# Pi1541_IEC.net
KiCad netlist of a schematic drawn in EAGLE
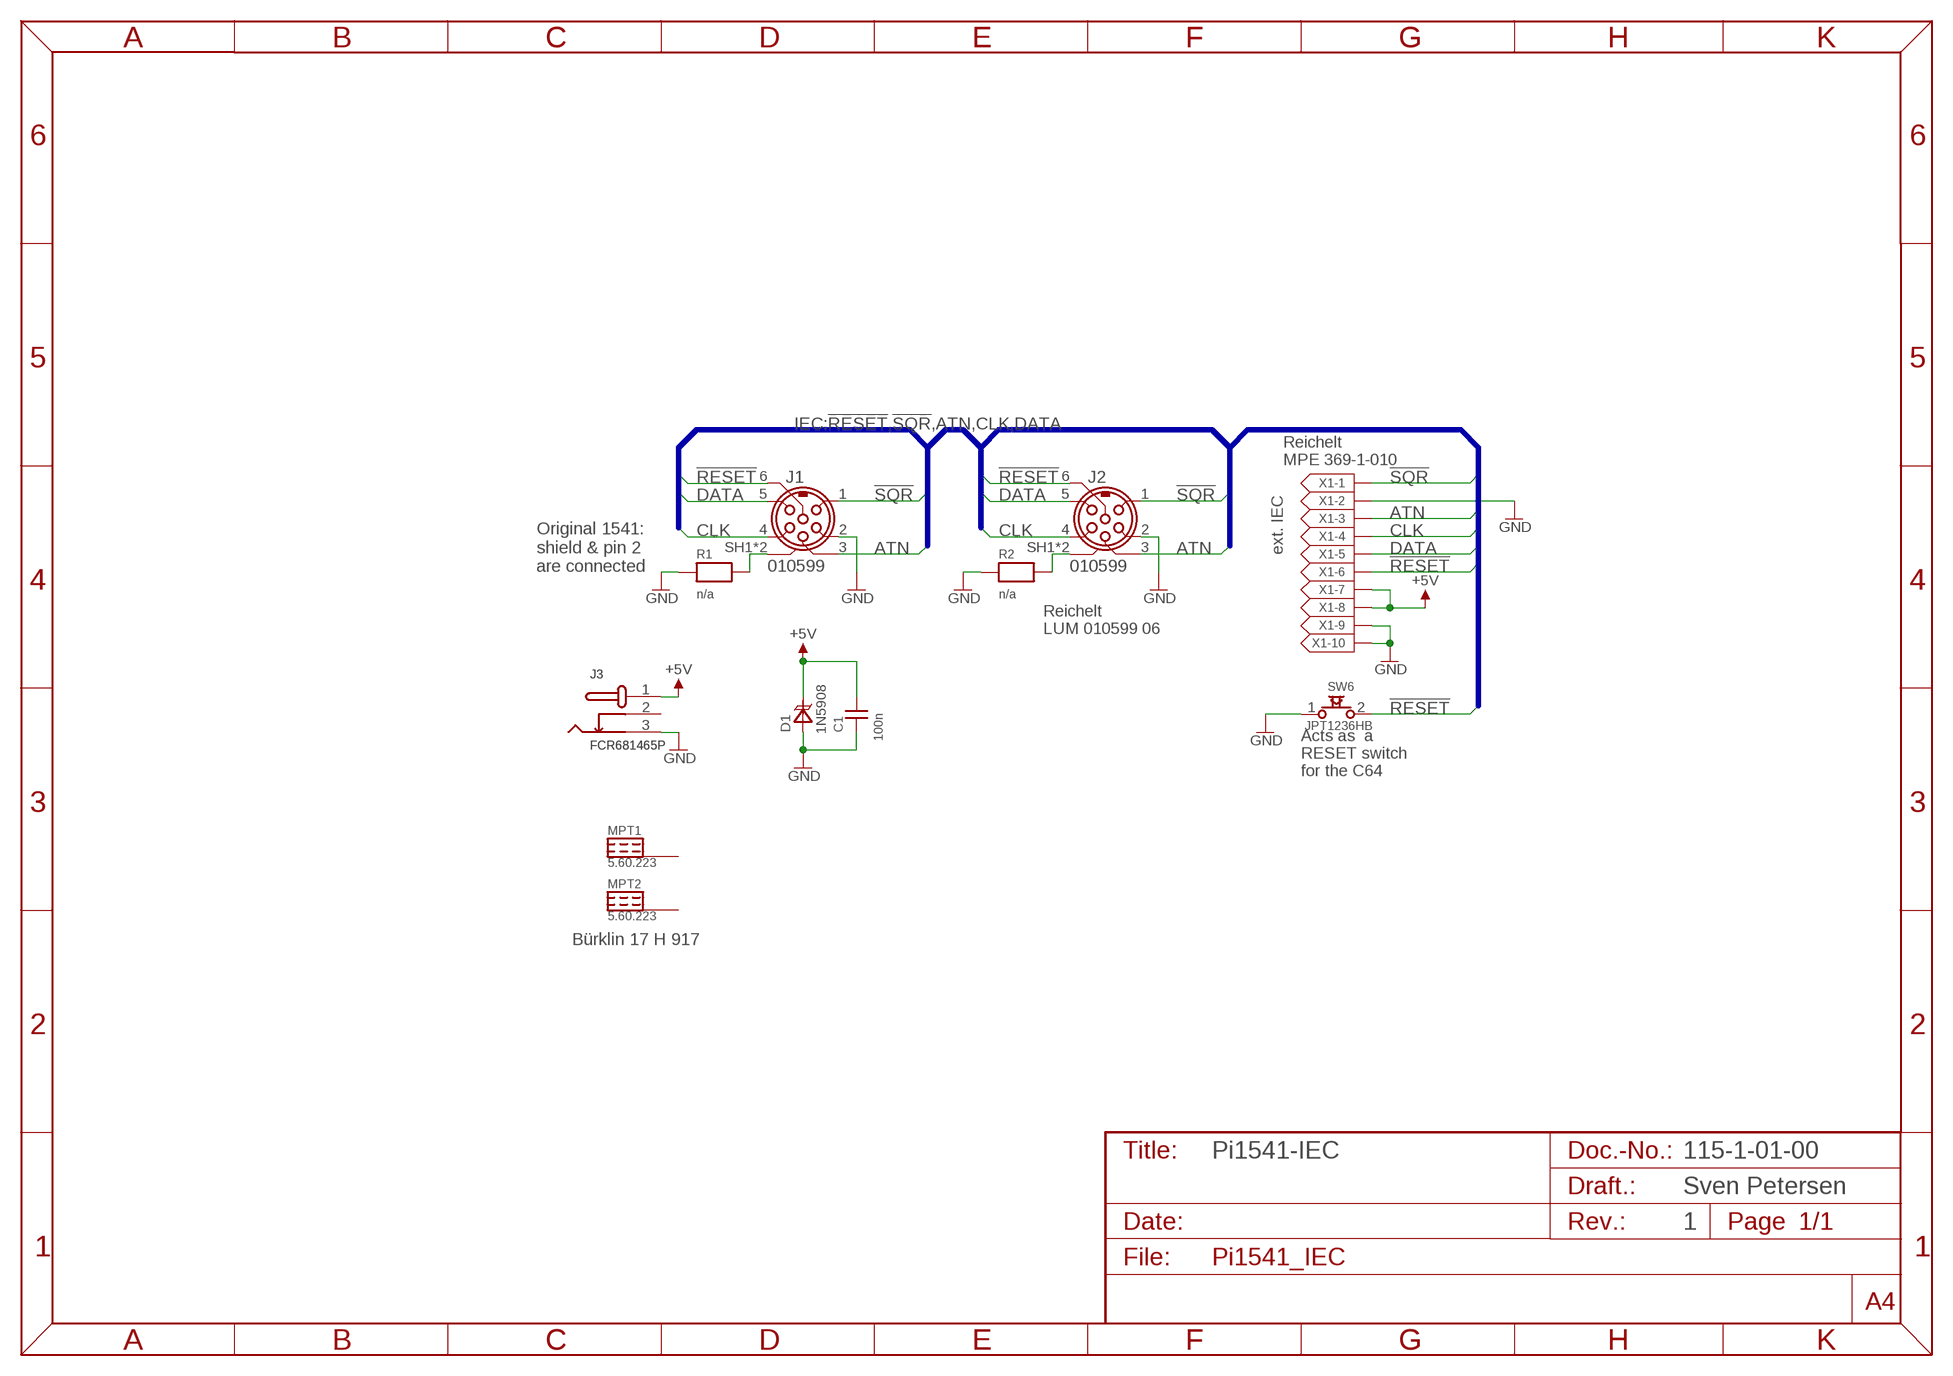
[diagram p0: schematic, sheet 1]

(export (version "E")
  (design (tool "Eeschema 10.0.6"))
  (components
    (comp (ref "C1")
      (value "100n")
      (footprint "eagle-import:C-2,5")
      (libsource (lib "eagle-import") (part "CAP01"))
    )
    (comp (ref "D1")
      (value "1N5908")
      (footprint "eagle-import:CB429")
      (libsource (lib "eagle-import") (part "1N5908"))
    )
    (comp (ref "J1")
      (value "010599")
      (footprint "eagle-import:010599")
      (libsource (lib "eagle-import") (part "010599"))
    )
    (comp (ref "J2")
      (value "010599")
      (footprint "eagle-import:010599")
      (libsource (lib "eagle-import") (part "010599"))
    )
    (comp (ref "J3")
      (value "FCR681465P")
      (footprint "eagle-import:FCR681465P")
      (libsource (lib "eagle-import") (part "FCR681465P"))
    )
    (comp (ref "MPT1")
      (value "5.60.223")
      (footprint "eagle-import:5.60.223")
      (libsource (lib "eagle-import") (part "5.60.223"))
    )
    (comp (ref "MPT2")
      (value "5.60.223")
      (footprint "eagle-import:5.60.223")
      (libsource (lib "eagle-import") (part "5.60.223"))
    )
    (comp (ref "R1")
      (value "n/a")
      (footprint "eagle-import:0805")
      (libsource (lib "eagle-import") (part "R-0805"))
    )
    (comp (ref "R2")
      (value "n/a")
      (footprint "eagle-import:0805")
      (libsource (lib "eagle-import") (part "R-0805"))
    )
    (comp (ref "SW6")
      (value "JPT1236HB")
      (footprint "eagle-import:JTP_1236HB")
      (libsource (lib "eagle-import") (part "JPT1236HB"))
    )
    (comp (ref "X1")
      (value "369-1-010")
      (footprint "eagle-import:MICMA10B")
      (libsource (lib "eagle-import") (part "MICMA10B-THT"))
    )
  )
  (nets
    (net (code "2") (name "+5V") (class "Default")
      (node (ref "C1") (pin "2") (pinfunction "2_2") (pintype "passive"))
      (node (ref "D1") (pin "K") (pinfunction "K_K") (pintype "passive"))
      (node (ref "J3") (pin "1") (pinfunction "1_1") (pintype "bidirectional"))
      (node (ref "X1") (pin "7") (pinfunction "1_7") (pintype "bidirectional"))
      (node (ref "X1") (pin "8") (pinfunction "1_8") (pintype "bidirectional"))
    )
    (net (code "3") (name "/ATN") (class "Default")
      (node (ref "J1") (pin "3") (pinfunction "3_3") (pintype "bidirectional"))
      (node (ref "J2") (pin "3") (pinfunction "3_3") (pintype "bidirectional"))
      (node (ref "X1") (pin "3") (pinfunction "1_3") (pintype "bidirectional"))
    )
    (net (code "4") (name "/CLK") (class "Default")
      (node (ref "J1") (pin "4") (pinfunction "4_4") (pintype "bidirectional"))
      (node (ref "J2") (pin "4") (pinfunction "4_4") (pintype "bidirectional"))
      (node (ref "X1") (pin "4") (pinfunction "1_4") (pintype "bidirectional"))
    )
    (net (code "5") (name "/DATA") (class "Default")
      (node (ref "J1") (pin "5") (pinfunction "5_5") (pintype "bidirectional"))
      (node (ref "J2") (pin "5") (pinfunction "5_5") (pintype "bidirectional"))
      (node (ref "X1") (pin "5") (pinfunction "1_5") (pintype "bidirectional"))
    )
    (net (code "7") (name "/~{RESET}") (class "Default")
      (node (ref "J1") (pin "6") (pinfunction "6_6") (pintype "bidirectional"))
      (node (ref "J2") (pin "6") (pinfunction "6_6") (pintype "bidirectional"))
      (node (ref "SW6") (pin "2") (pinfunction "2_2") (pintype "passive"))
      (node (ref "X1") (pin "6") (pinfunction "1_6") (pintype "bidirectional"))
    )
    (net (code "8") (name "/~{SQR}") (class "Default")
      (node (ref "J1") (pin "1") (pinfunction "1_1") (pintype "bidirectional"))
      (node (ref "J2") (pin "1") (pinfunction "1_1") (pintype "bidirectional"))
      (node (ref "X1") (pin "1") (pinfunction "1_1") (pintype "bidirectional"))
    )
    (net (code "9") (name "GND") (class "Default")
      (node (ref "C1") (pin "1") (pinfunction "1_1") (pintype "passive"))
      (node (ref "D1") (pin "A") (pinfunction "A_A") (pintype "passive"))
      (node (ref "J1") (pin "2") (pinfunction "2_2") (pintype "bidirectional"))
      (node (ref "J2") (pin "2") (pinfunction "2_2") (pintype "bidirectional"))
      (node (ref "J3") (pin "3") (pinfunction "3_3") (pintype "bidirectional"))
      (node (ref "R1") (pin "1") (pinfunction "1_1") (pintype "passive"))
      (node (ref "R2") (pin "1") (pinfunction "1_1") (pintype "passive"))
      (node (ref "SW6") (pin "1") (pinfunction "1_1") (pintype "passive"))
      (node (ref "X1") (pin "10") (pinfunction "1_10") (pintype "bidirectional"))
      (node (ref "X1") (pin "2") (pinfunction "1_2") (pintype "bidirectional"))
      (node (ref "X1") (pin "9") (pinfunction "1_9") (pintype "bidirectional"))
    )
    (net (code "10") (name "Net-(J1-SH-PadSH1)") (class "Default")
      (node (ref "J1") (pin "SH1") (pinfunction "SH_SH1") (pintype "bidirectional"))
      (node (ref "J1") (pin "SH2") (pinfunction "SH_SH2") (pintype "bidirectional"))
      (node (ref "R1") (pin "2") (pinfunction "2_2") (pintype "passive"))
    )
    (net (code "11") (name "Net-(J2-SH-PadSH1)") (class "Default")
      (node (ref "J2") (pin "SH1") (pinfunction "SH_SH1") (pintype "bidirectional"))
      (node (ref "J2") (pin "SH2") (pinfunction "SH_SH2") (pintype "bidirectional"))
      (node (ref "R2") (pin "2") (pinfunction "2_2") (pintype "passive"))
    )
    (net (code "12") (name "unconnected-(J3-Pad2)") (class "Default")
      (node (ref "J3") (pin "2") (pinfunction "2_2") (pintype "bidirectional"))
    )
    (net (code "13") (name "unconnected-(MPT1-P$1-Pad1)") (class "Default")
      (node (ref "MPT1") (pin "1") (pinfunction "P$1_1") (pintype "bidirectional"))
    )
    (net (code "14") (name "unconnected-(MPT2-P$1-Pad1)") (class "Default")
      (node (ref "MPT2") (pin "1") (pinfunction "P$1_1") (pintype "bidirectional"))
    )
  )
)
